# GasSensorModule_v2_2.net
KiCad netlist of a schematic drawn in EAGLE
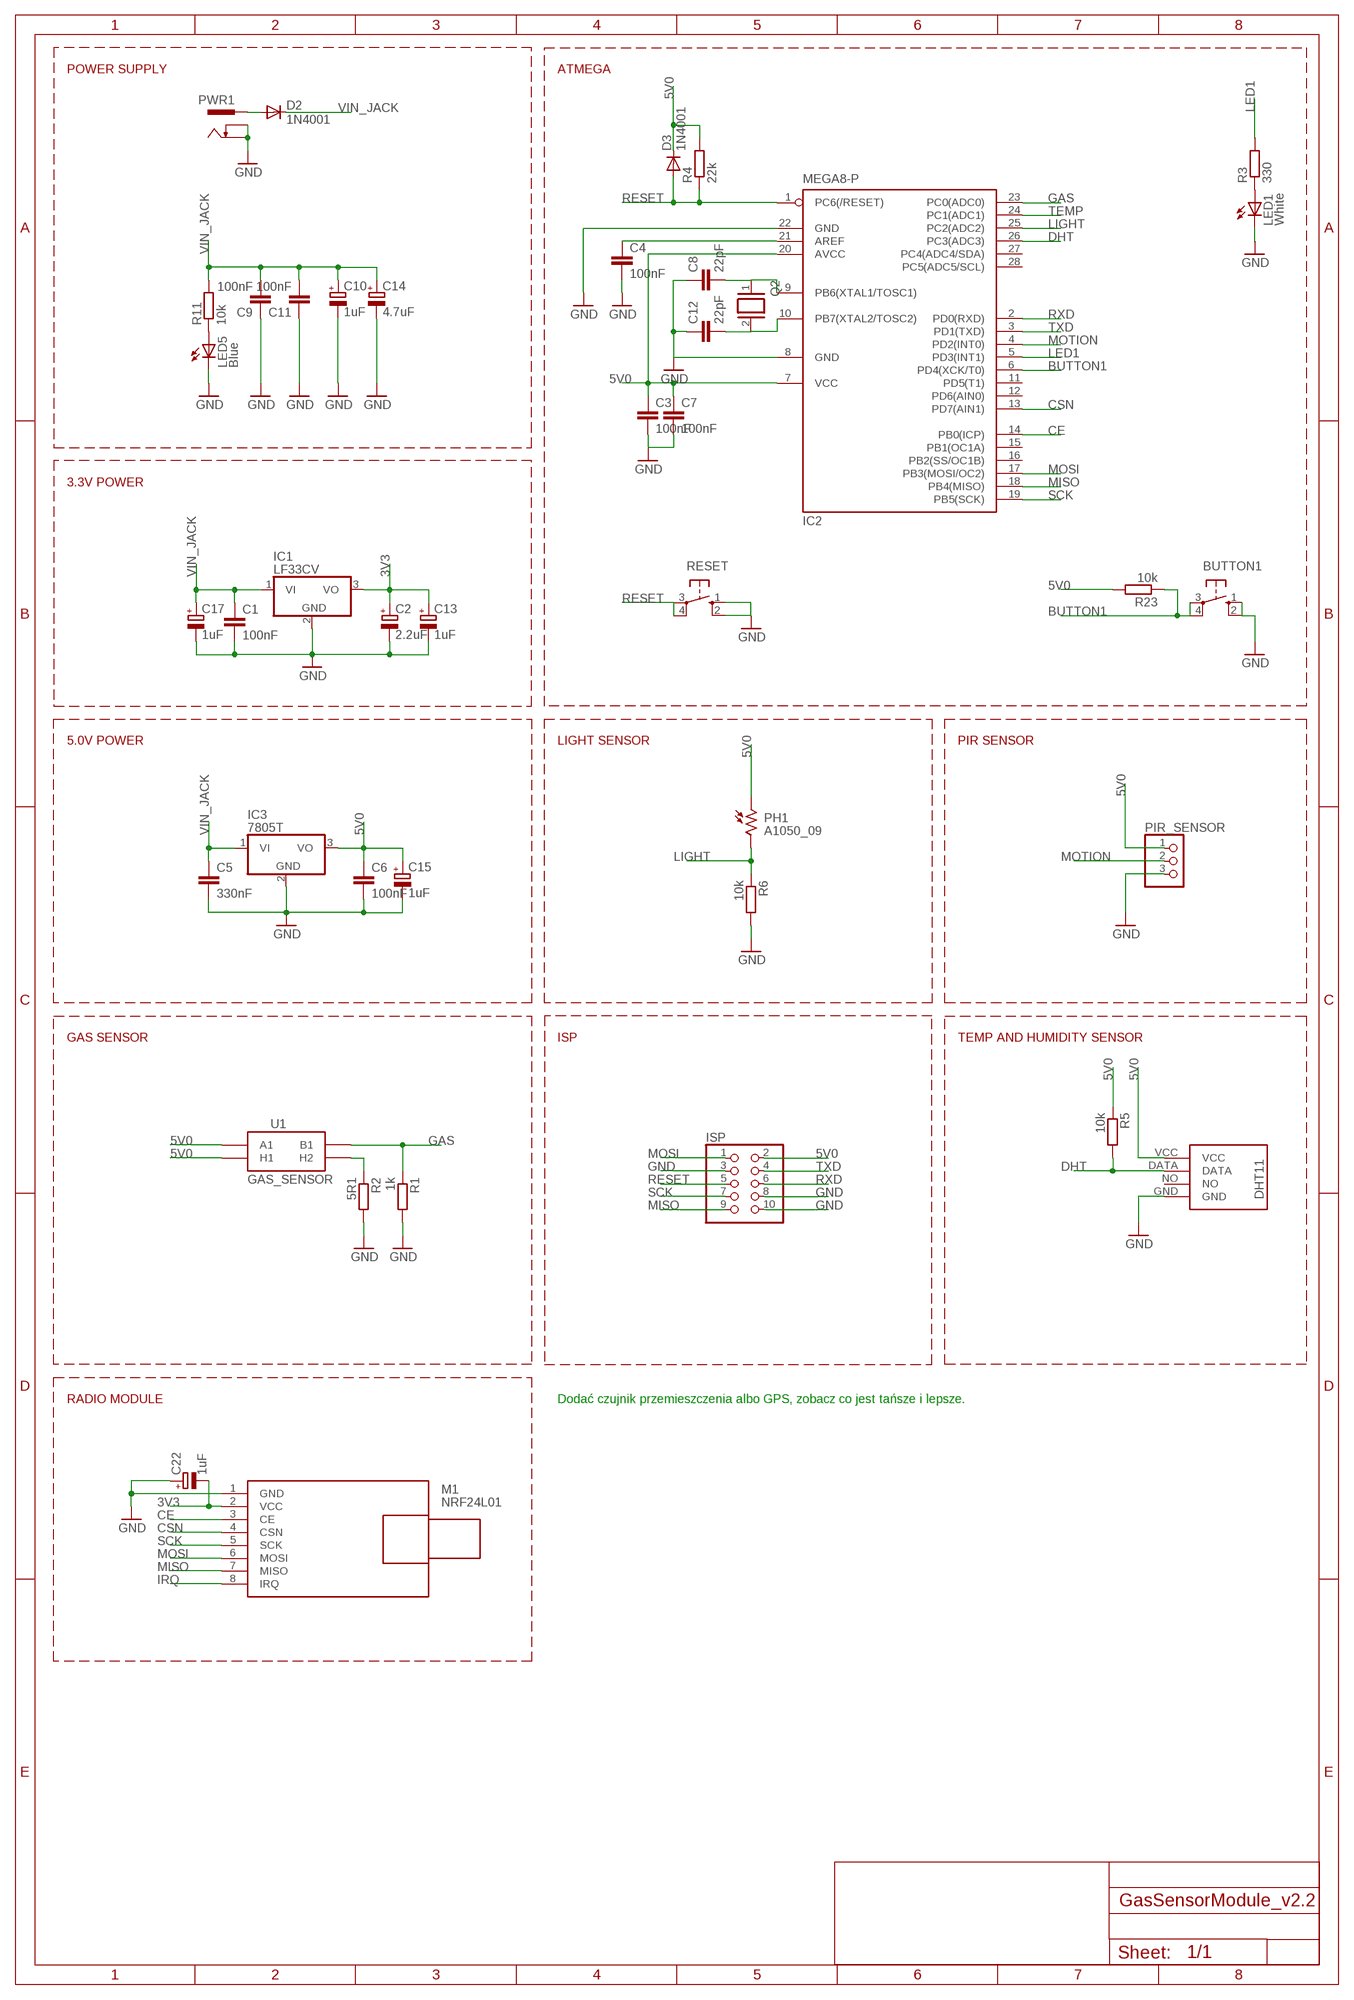
[diagram p0: schematic, sheet 1]

(export (version "E")
  (design (tool "Eeschema 10.0.6"))
  (components
    (comp (ref "BUTTON1")
      (value "10-XX")
      (footprint "eagle-import:B3F-10XX")
      (fields (field (name "MPN") "B3F-1000"))
      (libsource (lib "eagle-import") (part "10-XX"))
    )
    (comp (ref "C1")
      (value "100nF")
      (footprint "eagle-import:C025-025X050")
      (libsource (lib "eagle-import") (part "C-EU025-025X050"))
    )
    (comp (ref "C2")
      (value "2.2uF")
      (footprint "eagle-import:E2,5-5")
      (libsource (lib "eagle-import") (part "CPOL-EUE2.5-5"))
    )
    (comp (ref "C3")
      (value "100nF")
      (footprint "eagle-import:C025-025X050")
      (libsource (lib "eagle-import") (part "C-EU025-025X050"))
    )
    (comp (ref "C4")
      (value "100nF")
      (footprint "eagle-import:C025-025X050")
      (libsource (lib "eagle-import") (part "C-EU025-025X050"))
    )
    (comp (ref "C5")
      (value "330nF")
      (footprint "eagle-import:C025-025X050")
      (libsource (lib "eagle-import") (part "C-EU025-025X050"))
    )
    (comp (ref "C6")
      (value "100nF")
      (footprint "eagle-import:C025-025X050")
      (libsource (lib "eagle-import") (part "C-EU025-025X050"))
    )
    (comp (ref "C7")
      (value "100nF")
      (footprint "eagle-import:C025-025X050")
      (libsource (lib "eagle-import") (part "C-EU025-025X050"))
    )
    (comp (ref "C8")
      (value "22pF")
      (footprint "eagle-import:C025-025X050")
      (libsource (lib "eagle-import") (part "C-EU025-025X050"))
    )
    (comp (ref "C9")
      (value "100nF")
      (footprint "eagle-import:C025-025X050")
      (libsource (lib "eagle-import") (part "C-EU025-025X050"))
    )
    (comp (ref "C10")
      (value "1uF")
      (footprint "eagle-import:E2,5-5")
      (libsource (lib "eagle-import") (part "CPOL-EUE2.5-5"))
    )
    (comp (ref "C11")
      (value "100nF")
      (footprint "eagle-import:C025-025X050")
      (libsource (lib "eagle-import") (part "C-EU025-025X050"))
    )
    (comp (ref "C12")
      (value "22pF")
      (footprint "eagle-import:C025-025X050")
      (libsource (lib "eagle-import") (part "C-EU025-025X050"))
    )
    (comp (ref "C13")
      (value "1uF")
      (footprint "eagle-import:E2,5-5")
      (libsource (lib "eagle-import") (part "CPOL-EUE2.5-5"))
    )
    (comp (ref "C14")
      (value "4.7uF")
      (footprint "eagle-import:E2,5-5")
      (libsource (lib "eagle-import") (part "CPOL-EUE2.5-5"))
    )
    (comp (ref "C15")
      (value "1uF")
      (footprint "eagle-import:E2,5-5")
      (libsource (lib "eagle-import") (part "CPOL-EUE2.5-5"))
    )
    (comp (ref "C17")
      (value "1uF")
      (footprint "eagle-import:E2,5-5")
      (libsource (lib "eagle-import") (part "CPOL-EUE2.5-5"))
    )
    (comp (ref "C22")
      (value "1uF")
      (footprint "eagle-import:E2,5-5")
      (libsource (lib "eagle-import") (part "CPOL-EUE2.5-5"))
    )
    (comp (ref "D2")
      (value "1N4001")
      (footprint "eagle-import:DO41-10")
      (libsource (lib "eagle-import") (part "1N4004"))
    )
    (comp (ref "D3")
      (value "1N4001")
      (footprint "eagle-import:DO41-10")
      (libsource (lib "eagle-import") (part "1N4004"))
    )
    (comp (ref "IC1")
      (value "LF33CV")
      (footprint "eagle-import:TO220H")
      (libsource (lib "eagle-import") (part "78T05"))
    )
    (comp (ref "IC2")
      (value "MEGA8-P")
      (footprint "eagle-import:DIL28-3")
      (libsource (lib "eagle-import") (part "MEGA8-P"))
    )
    (comp (ref "IC3")
      (value "7805T")
      (footprint "eagle-import:TO220H")
      (libsource (lib "eagle-import") (part "78T05"))
    )
    (comp (ref "ISP")
      (value "PINHD-2X5")
      (footprint "eagle-import:2X05")
      (libsource (lib "eagle-import") (part "PINHD-2X5"))
    )
    (comp (ref "LED1")
      (value "White")
      (footprint "eagle-import:LED3MM")
      (libsource (lib "eagle-import") (part "LED3MM"))
    )
    (comp (ref "LED5")
      (value "Blue")
      (footprint "eagle-import:LED3MM")
      (libsource (lib "eagle-import") (part "LED3MM"))
    )
    (comp (ref "M1")
      (value "NRF24L01")
      (footprint "eagle-import:WIRELESS-NRD24L01-PA-EXT")
      (libsource (lib "eagle-import") (part "WIRELESS-NRF24L01-PA-EXT"))
    )
    (comp (ref "PH1")
      (value "A1050_09")
      (footprint "eagle-import:T0-46-A10XX")
      (libsource (lib "eagle-import") (part "A1050_09"))
    )
    (comp (ref "PIR_SENSOR")
      (value "PINHD-1X3")
      (footprint "eagle-import:1X03")
      (libsource (lib "eagle-import") (part "PINHD-1X3"))
    )
    (comp (ref "PWR1")
      (value "PWR-JAKPWR_JACK_UNI_MILLING")
      (footprint "eagle-import:PWR_JACK_UNI_MILLING")
      (libsource (lib "eagle-import") (part "PWR-JAKPWR_JACK_UNI_MILLING"))
    )
    (comp (ref "Q2")
      (value "XTAL/S")
      (footprint "eagle-import:QS")
      (libsource (lib "eagle-import") (part "XTAL/S"))
    )
    (comp (ref "R1")
      (value "1k")
      (footprint "eagle-import:0207_10")
      (libsource (lib "eagle-import") (part "R-EU_0207/10"))
    )
    (comp (ref "R2")
      (value "5R1")
      (footprint "eagle-import:0207_10")
      (libsource (lib "eagle-import") (part "R-EU_0207/10"))
    )
    (comp (ref "R3")
      (value "330")
      (footprint "eagle-import:0207_10")
      (libsource (lib "eagle-import") (part "R-EU_0207/10"))
    )
    (comp (ref "R4")
      (value "22k")
      (footprint "eagle-import:0207_10")
      (libsource (lib "eagle-import") (part "R-EU_0207/10"))
    )
    (comp (ref "R5")
      (value "10k")
      (footprint "eagle-import:0207_10")
      (libsource (lib "eagle-import") (part "R-EU_0207/10"))
    )
    (comp (ref "R6")
      (value "10k")
      (footprint "eagle-import:0207_10")
      (libsource (lib "eagle-import") (part "R-EU_0207/10"))
    )
    (comp (ref "R11")
      (value "10k")
      (footprint "eagle-import:0207_10")
      (libsource (lib "eagle-import") (part "R-EU_0207/10"))
    )
    (comp (ref "R23")
      (value "10k")
      (footprint "eagle-import:0207_10")
      (libsource (lib "eagle-import") (part "R-EU_0207/10"))
    )
    (comp (ref "RESET")
      (value "10-XX")
      (footprint "eagle-import:B3F-10XX")
      (fields (field (name "MPN") "B3F-1000"))
      (libsource (lib "eagle-import") (part "10-XX"))
    )
    (comp (ref "U$1")
      (value "DHT11-PION.")
      (footprint "eagle-import:DHT11-PION.")
      (libsource (lib "eagle-import") (part "DHT11-PION."))
    )
    (comp (ref "U1")
      (value "GAS_SENSOR")
      (footprint "eagle-import:MQ-3")
      (libsource (lib "eagle-import") (part "GAS_SENSOR"))
    )
  )
  (nets
    (net (code "1") (name "/3V3") (class "Default")
      (node (ref "C13") (pin "+") (pinfunction "+_+") (pintype "passive"))
      (node (ref "C2") (pin "+") (pinfunction "+_+") (pintype "passive"))
      (node (ref "C22") (pin "-") (pinfunction "-_-") (pintype "passive"))
      (node (ref "IC1") (pin "3") (pinfunction "VO_3") (pintype "passive"))
      (node (ref "M1") (pin "2") (pinfunction "VCC_2") (pintype "power_in"))
    )
    (net (code "2") (name "/5V0") (class "Default")
      (node (ref "C15") (pin "+") (pinfunction "+_+") (pintype "passive"))
      (node (ref "C3") (pin "1") (pinfunction "1_1") (pintype "passive"))
      (node (ref "C6") (pin "1") (pinfunction "1_1") (pintype "passive"))
      (node (ref "C7") (pin "1") (pinfunction "1_1") (pintype "passive"))
      (node (ref "D3") (pin "C") (pinfunction "C_C") (pintype "passive"))
      (node (ref "IC2") (pin "20") (pinfunction "AVCC_20") (pintype "power_in"))
      (node (ref "IC2") (pin "7") (pinfunction "VCC_7") (pintype "power_in"))
      (node (ref "IC3") (pin "3") (pinfunction "VO_3") (pintype "passive"))
      (node (ref "ISP") (pin "2") (pinfunction "2_2") (pintype "passive"))
      (node (ref "PH1") (pin "1") (pinfunction "1_1") (pintype "passive"))
      (node (ref "PIR_SENSOR") (pin "1") (pinfunction "1_1") (pintype "passive"))
      (node (ref "R23") (pin "2") (pinfunction "2_2") (pintype "passive"))
      (node (ref "R4") (pin "2") (pinfunction "2_2") (pintype "passive"))
      (node (ref "R5") (pin "1") (pinfunction "1_1") (pintype "passive"))
      (node (ref "U$1") (pin "VCC") (pinfunction "VCC_VCC") (pintype "bidirectional"))
      (node (ref "U1") (pin "A1") (pinfunction "A1_A1") (pintype "bidirectional"))
      (node (ref "U1") (pin "HA") (pinfunction "H1_HA") (pintype "bidirectional"))
    )
    (net (code "3") (name "/BUTTON1") (class "Default")
      (node (ref "BUTTON1") (pin "3") (pinfunction "P_3") (pintype "passive"))
      (node (ref "BUTTON1") (pin "4") (pinfunction "P1_4") (pintype "passive"))
      (node (ref "IC2") (pin "6") (pinfunction "PD4(XCK/T0)_6") (pintype "bidirectional"))
      (node (ref "R23") (pin "1") (pinfunction "1_1") (pintype "passive"))
    )
    (net (code "4") (name "/CE") (class "Default")
      (node (ref "IC2") (pin "14") (pinfunction "PB0(ICP)_14") (pintype "bidirectional"))
      (node (ref "M1") (pin "3") (pinfunction "CE_3") (pintype "bidirectional"))
    )
    (net (code "5") (name "/CSN") (class "Default")
      (node (ref "IC2") (pin "13") (pinfunction "PD7(AIN1)_13") (pintype "bidirectional"))
      (node (ref "M1") (pin "4") (pinfunction "CSN_4") (pintype "bidirectional"))
    )
    (net (code "6") (name "/DHT") (class "Default")
      (node (ref "IC2") (pin "26") (pinfunction "PC3(ADC3)_26") (pintype "bidirectional"))
      (node (ref "R5") (pin "2") (pinfunction "2_2") (pintype "passive"))
      (node (ref "U$1") (pin "DATA") (pinfunction "DATA_DATA") (pintype "bidirectional"))
    )
    (net (code "7") (name "/GAS") (class "Default")
      (node (ref "IC2") (pin "23") (pinfunction "PC0(ADC0)_23") (pintype "bidirectional"))
      (node (ref "R1") (pin "1") (pinfunction "1_1") (pintype "passive"))
      (node (ref "U1") (pin "B1") (pinfunction "B1_B1") (pintype "bidirectional"))
    )
    (net (code "8") (name "/IRQ") (class "Default")
      (node (ref "M1") (pin "8") (pinfunction "IRQ_8") (pintype "bidirectional"))
    )
    (net (code "9") (name "/LED1") (class "Default")
      (node (ref "IC2") (pin "5") (pinfunction "PD3(INT1)_5") (pintype "bidirectional"))
      (node (ref "R3") (pin "2") (pinfunction "2_2") (pintype "passive"))
    )
    (net (code "10") (name "/LIGHT") (class "Default")
      (node (ref "IC2") (pin "25") (pinfunction "PC2(ADC2)_25") (pintype "bidirectional"))
      (node (ref "PH1") (pin "2") (pinfunction "2_2") (pintype "passive"))
      (node (ref "R6") (pin "1") (pinfunction "1_1") (pintype "passive"))
    )
    (net (code "11") (name "/MISO") (class "Default")
      (node (ref "IC2") (pin "18") (pinfunction "PB4(MISO)_18") (pintype "bidirectional"))
      (node (ref "ISP") (pin "9") (pinfunction "9_9") (pintype "passive"))
      (node (ref "M1") (pin "7") (pinfunction "MISO_7") (pintype "bidirectional"))
    )
    (net (code "12") (name "/MOSI") (class "Default")
      (node (ref "IC2") (pin "17") (pinfunction "PB3(MOSI/OC2)_17") (pintype "bidirectional"))
      (node (ref "ISP") (pin "1") (pinfunction "1_1") (pintype "passive"))
      (node (ref "M1") (pin "6") (pinfunction "MOSI_6") (pintype "bidirectional"))
    )
    (net (code "13") (name "/MOTION") (class "Default")
      (node (ref "IC2") (pin "4") (pinfunction "PD2(INT0)_4") (pintype "bidirectional"))
      (node (ref "PIR_SENSOR") (pin "2") (pinfunction "2_2") (pintype "passive"))
    )
    (net (code "14") (name "/RESET") (class "Default")
      (node (ref "D3") (pin "A") (pinfunction "A_A") (pintype "passive"))
      (node (ref "IC2") (pin "1") (pinfunction "PC6(/RESET)_1") (pintype "bidirectional"))
      (node (ref "ISP") (pin "5") (pinfunction "5_5") (pintype "passive"))
      (node (ref "R4") (pin "1") (pinfunction "1_1") (pintype "passive"))
      (node (ref "RESET") (pin "3") (pinfunction "P_3") (pintype "passive"))
      (node (ref "RESET") (pin "4") (pinfunction "P1_4") (pintype "passive"))
    )
    (net (code "15") (name "/RXD") (class "Default")
      (node (ref "IC2") (pin "2") (pinfunction "PD0(RXD)_2") (pintype "bidirectional"))
      (node (ref "ISP") (pin "6") (pinfunction "6_6") (pintype "passive"))
    )
    (net (code "16") (name "/SCK") (class "Default")
      (node (ref "IC2") (pin "19") (pinfunction "PB5(SCK)_19") (pintype "bidirectional"))
      (node (ref "ISP") (pin "7") (pinfunction "7_7") (pintype "passive"))
      (node (ref "M1") (pin "5") (pinfunction "SCK_5") (pintype "bidirectional"))
    )
    (net (code "17") (name "/TEMP") (class "Default")
      (node (ref "IC2") (pin "24") (pinfunction "PC1(ADC1)_24") (pintype "bidirectional"))
    )
    (net (code "18") (name "/TXD") (class "Default")
      (node (ref "IC2") (pin "3") (pinfunction "PD1(TXD)_3") (pintype "bidirectional"))
      (node (ref "ISP") (pin "4") (pinfunction "4_4") (pintype "passive"))
    )
    (net (code "19") (name "/VIN_JACK") (class "Default")
      (node (ref "C1") (pin "1") (pinfunction "1_1") (pintype "passive"))
      (node (ref "C10") (pin "+") (pinfunction "+_+") (pintype "passive"))
      (node (ref "C11") (pin "2") (pinfunction "2_2") (pintype "passive"))
      (node (ref "C14") (pin "+") (pinfunction "+_+") (pintype "passive"))
      (node (ref "C17") (pin "+") (pinfunction "+_+") (pintype "passive"))
      (node (ref "C5") (pin "1") (pinfunction "1_1") (pintype "passive"))
      (node (ref "C9") (pin "2") (pinfunction "2_2") (pintype "passive"))
      (node (ref "D2") (pin "C") (pinfunction "C_C") (pintype "passive"))
      (node (ref "IC1") (pin "1") (pinfunction "VI_1") (pintype "input"))
      (node (ref "IC3") (pin "1") (pinfunction "VI_1") (pintype "input"))
      (node (ref "R11") (pin "2") (pinfunction "2_2") (pintype "passive"))
    )
    (net (code "20") (name "GND") (class "Default")
      (node (ref "BUTTON1") (pin "1") (pinfunction "S_1") (pintype "passive"))
      (node (ref "BUTTON1") (pin "2") (pinfunction "S1_2") (pintype "passive"))
      (node (ref "C1") (pin "2") (pinfunction "2_2") (pintype "passive"))
      (node (ref "C10") (pin "-") (pinfunction "-_-") (pintype "passive"))
      (node (ref "C11") (pin "1") (pinfunction "1_1") (pintype "passive"))
      (node (ref "C12") (pin "1") (pinfunction "1_1") (pintype "passive"))
      (node (ref "C13") (pin "-") (pinfunction "-_-") (pintype "passive"))
      (node (ref "C14") (pin "-") (pinfunction "-_-") (pintype "passive"))
      (node (ref "C15") (pin "-") (pinfunction "-_-") (pintype "passive"))
      (node (ref "C17") (pin "-") (pinfunction "-_-") (pintype "passive"))
      (node (ref "C2") (pin "-") (pinfunction "-_-") (pintype "passive"))
      (node (ref "C22") (pin "+") (pinfunction "+_+") (pintype "passive"))
      (node (ref "C3") (pin "2") (pinfunction "2_2") (pintype "passive"))
      (node (ref "C4") (pin "2") (pinfunction "2_2") (pintype "passive"))
      (node (ref "C5") (pin "2") (pinfunction "2_2") (pintype "passive"))
      (node (ref "C6") (pin "2") (pinfunction "2_2") (pintype "passive"))
      (node (ref "C7") (pin "2") (pinfunction "2_2") (pintype "passive"))
      (node (ref "C8") (pin "1") (pinfunction "1_1") (pintype "passive"))
      (node (ref "C9") (pin "1") (pinfunction "1_1") (pintype "passive"))
      (node (ref "IC1") (pin "2") (pinfunction "GND_2") (pintype "passive"))
      (node (ref "IC2") (pin "22") (pinfunction "GND_22") (pintype "power_in"))
      (node (ref "IC2") (pin "8") (pinfunction "GND_8") (pintype "power_in"))
      (node (ref "IC3") (pin "2") (pinfunction "GND_2") (pintype "passive"))
      (node (ref "ISP") (pin "10") (pinfunction "10_10") (pintype "passive"))
      (node (ref "ISP") (pin "3") (pinfunction "3_3") (pintype "passive"))
      (node (ref "ISP") (pin "8") (pinfunction "8_8") (pintype "passive"))
      (node (ref "LED1") (pin "K") (pinfunction "C_K") (pintype "passive"))
      (node (ref "LED5") (pin "K") (pinfunction "C_K") (pintype "passive"))
      (node (ref "M1") (pin "1") (pinfunction "GND_1") (pintype "power_in"))
      (node (ref "PIR_SENSOR") (pin "3") (pinfunction "3_3") (pintype "passive"))
      (node (ref "PWR1") (pin "-") (pinfunction "-_-") (pintype "passive"))
      (node (ref "PWR1") (pin "--") (pinfunction "--_--") (pintype "passive"))
      (node (ref "R1") (pin "2") (pinfunction "2_2") (pintype "passive"))
      (node (ref "R2") (pin "2") (pinfunction "2_2") (pintype "passive"))
      (node (ref "R6") (pin "2") (pinfunction "2_2") (pintype "passive"))
      (node (ref "RESET") (pin "1") (pinfunction "S_1") (pintype "passive"))
      (node (ref "RESET") (pin "2") (pinfunction "S1_2") (pintype "passive"))
      (node (ref "U$1") (pin "GND") (pinfunction "GND_GND") (pintype "bidirectional"))
    )
    (net (code "21") (name "Net-(D2-PadA)") (class "Default")
      (node (ref "D2") (pin "A") (pinfunction "A_A") (pintype "passive"))
      (node (ref "PWR1") (pin "+") (pinfunction "+_+") (pintype "passive"))
    )
    (net (code "22") (name "Net-(IC2-AREF)") (class "Default")
      (node (ref "C4") (pin "1") (pinfunction "1_1") (pintype "passive"))
      (node (ref "IC2") (pin "21") (pinfunction "AREF_21") (pintype "passive"))
    )
    (net (code "23") (name "Net-(IC2-PB6(XTAL1{slash}TOSC1))") (class "Default")
      (node (ref "C8") (pin "2") (pinfunction "2_2") (pintype "passive"))
      (node (ref "IC2") (pin "9") (pinfunction "PB6(XTAL1/TOSC1)_9") (pintype "bidirectional"))
      (node (ref "Q2") (pin "1") (pinfunction "1_1") (pintype "passive"))
    )
    (net (code "24") (name "Net-(IC2-PB7(XTAL2{slash}TOSC2))") (class "Default")
      (node (ref "C12") (pin "2") (pinfunction "2_2") (pintype "passive"))
      (node (ref "IC2") (pin "10") (pinfunction "PB7(XTAL2/TOSC2)_10") (pintype "bidirectional"))
      (node (ref "Q2") (pin "2") (pinfunction "2_2") (pintype "passive"))
    )
    (net (code "25") (name "Net-(LED1-PadA)") (class "Default")
      (node (ref "LED1") (pin "A") (pinfunction "A_A") (pintype "passive"))
      (node (ref "R3") (pin "1") (pinfunction "1_1") (pintype "passive"))
    )
    (net (code "26") (name "Net-(LED5-PadA)") (class "Default")
      (node (ref "LED5") (pin "A") (pinfunction "A_A") (pintype "passive"))
      (node (ref "R11") (pin "1") (pinfunction "1_1") (pintype "passive"))
    )
    (net (code "27") (name "Net-(U1-H2)") (class "Default")
      (node (ref "R2") (pin "1") (pinfunction "1_1") (pintype "passive"))
      (node (ref "U1") (pin "HB") (pinfunction "H2_HB") (pintype "bidirectional"))
    )
    (net (code "28") (name "unconnected-(IC2-PB1(OC1A)-Pad15)") (class "Default")
      (node (ref "IC2") (pin "15") (pinfunction "PB1(OC1A)_15") (pintype "bidirectional"))
    )
    (net (code "29") (name "unconnected-(IC2-PB2(SS{slash}OC1B)-Pad16)") (class "Default")
      (node (ref "IC2") (pin "16") (pinfunction "PB2(SS/OC1B)_16") (pintype "bidirectional"))
    )
    (net (code "30") (name "unconnected-(IC2-PC4(ADC4{slash}SDA)-Pad27)") (class "Default")
      (node (ref "IC2") (pin "27") (pinfunction "PC4(ADC4/SDA)_27") (pintype "bidirectional"))
    )
    (net (code "31") (name "unconnected-(IC2-PC5(ADC5{slash}SCL)-Pad28)") (class "Default")
      (node (ref "IC2") (pin "28") (pinfunction "PC5(ADC5/SCL)_28") (pintype "bidirectional"))
    )
    (net (code "32") (name "unconnected-(IC2-PD5(T1)-Pad11)") (class "Default")
      (node (ref "IC2") (pin "11") (pinfunction "PD5(T1)_11") (pintype "bidirectional"))
    )
    (net (code "33") (name "unconnected-(IC2-PD6(AIN0)-Pad12)") (class "Default")
      (node (ref "IC2") (pin "12") (pinfunction "PD6(AIN0)_12") (pintype "bidirectional"))
    )
    (net (code "34") (name "unconnected-(U$1-PadNO)") (class "Default")
      (node (ref "U$1") (pin "NO") (pinfunction "NO_NO") (pintype "bidirectional"))
    )
  )
)
